# my_tic_tac_toe_board.net
KiCad netlist of a schematic drawn in EAGLE
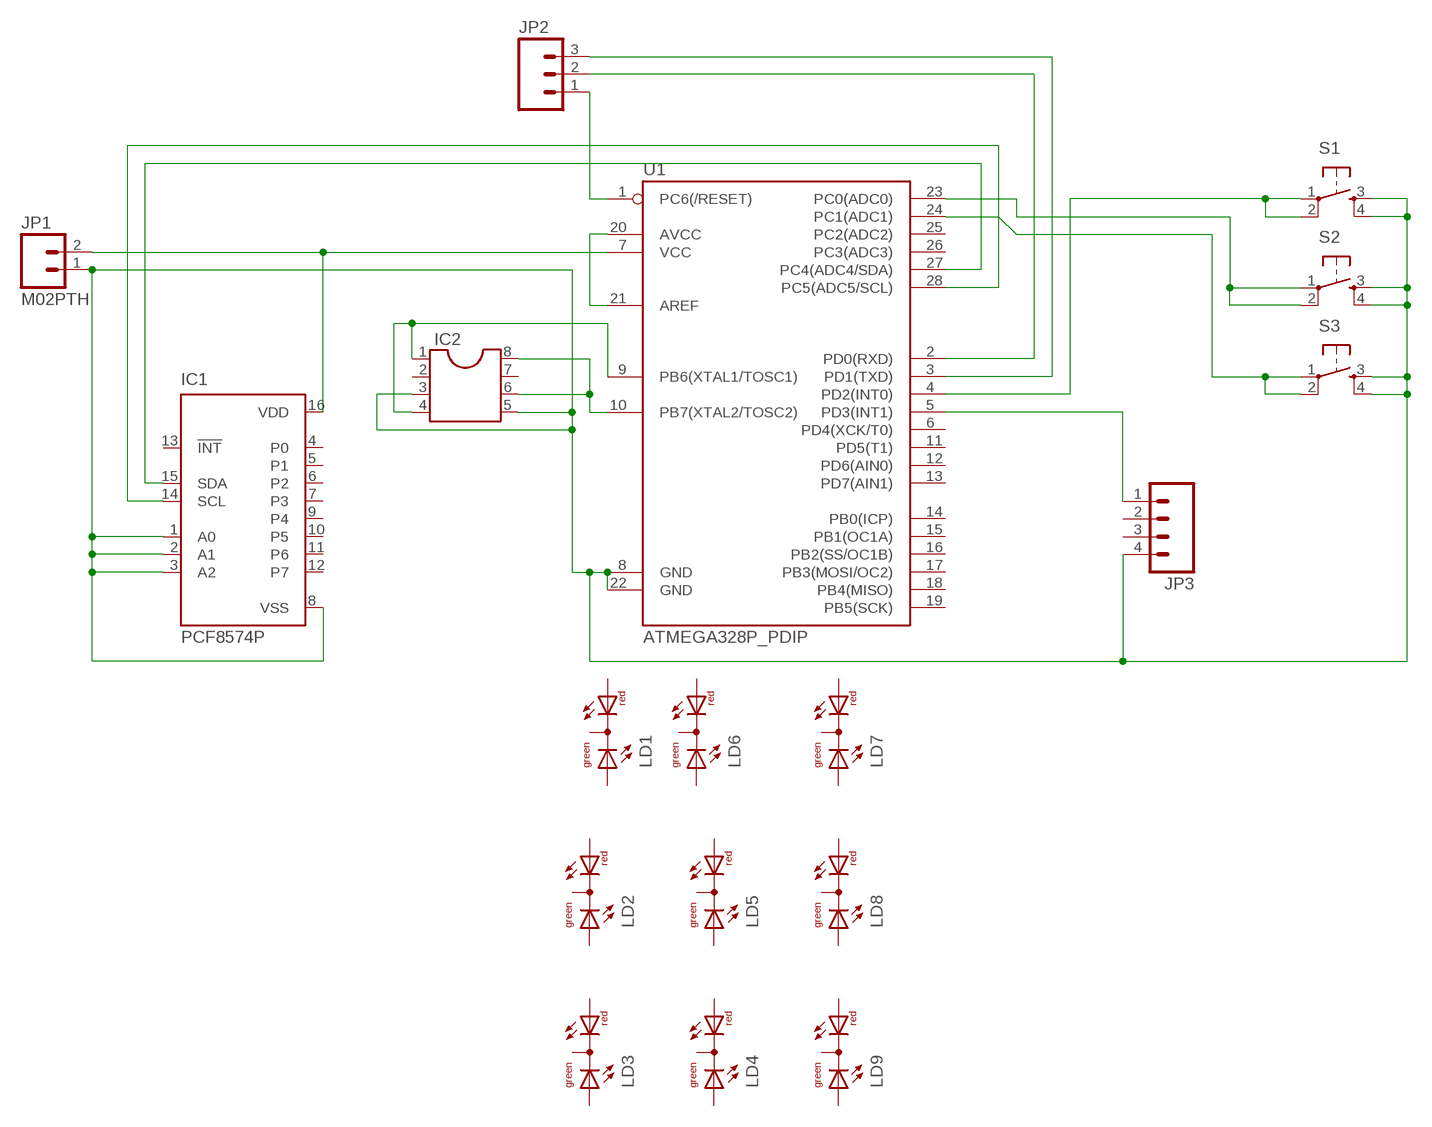
[diagram p0: schematic, sheet 1]

(export (version "E")
  (design (tool "Eeschema 10.0.6"))
  (components
    (comp (ref "IC1")
      (value "PCF8574P")
      (footprint "eagle-import:DIL16")
      (fields (field (name "MPN") "PCF8574PN"))
      (libsource (lib "eagle-import") (part "PCF8574P"))
    )
    (comp (ref "IC2")
      (value "DIL8S")
      (footprint "eagle-import:SOCKET-08")
      (libsource (lib "eagle-import") (part "DIL8S"))
    )
    (comp (ref "JP1")
      (value "M02PTH")
      (footprint "eagle-import:1X02")
      (libsource (lib "eagle-import") (part "M02PTH"))
    )
    (comp (ref "JP2")
      (value "M03PTH")
      (footprint "eagle-import:1X03")
      (libsource (lib "eagle-import") (part "M03PTH"))
    )
    (comp (ref "JP3")
      (value "M04PTH")
      (footprint "eagle-import:1X04")
      (libsource (lib "eagle-import") (part "M04PTH"))
    )
    (comp (ref "LD1")
      (value "DUOLED-RG-C")
      (footprint "eagle-import:DUOLED-C-5MM")
      (libsource (lib "eagle-import") (part "DUOLED-RG-C"))
    )
    (comp (ref "LD2")
      (value "DUOLED-RG-C")
      (footprint "eagle-import:DUOLED-C-5MM")
      (libsource (lib "eagle-import") (part "DUOLED-RG-C"))
    )
    (comp (ref "LD3")
      (value "DUOLED-RG-C")
      (footprint "eagle-import:DUOLED-C-5MM")
      (libsource (lib "eagle-import") (part "DUOLED-RG-C"))
    )
    (comp (ref "LD4")
      (value "DUOLED-RG-C")
      (footprint "eagle-import:DUOLED-C-5MM")
      (libsource (lib "eagle-import") (part "DUOLED-RG-C"))
    )
    (comp (ref "LD5")
      (value "DUOLED-RG-C")
      (footprint "eagle-import:DUOLED-C-5MM")
      (libsource (lib "eagle-import") (part "DUOLED-RG-C"))
    )
    (comp (ref "LD6")
      (value "DUOLED-RG-C")
      (footprint "eagle-import:DUOLED-C-5MM")
      (libsource (lib "eagle-import") (part "DUOLED-RG-C"))
    )
    (comp (ref "LD7")
      (value "DUOLED-RG-C")
      (footprint "eagle-import:DUOLED-C-5MM")
      (libsource (lib "eagle-import") (part "DUOLED-RG-C"))
    )
    (comp (ref "LD8")
      (value "DUOLED-RG-C")
      (footprint "eagle-import:DUOLED-C-5MM")
      (libsource (lib "eagle-import") (part "DUOLED-RG-C"))
    )
    (comp (ref "LD9")
      (value "DUOLED-RG-C")
      (footprint "eagle-import:DUOLED-C-5MM")
      (libsource (lib "eagle-import") (part "DUOLED-RG-C"))
    )
    (comp (ref "S1")
      (value "TAC_SWITCHPTH")
      (footprint "eagle-import:TACTILE-PTH")
      (libsource (lib "eagle-import") (part "TAC_SWITCHPTH"))
    )
    (comp (ref "S2")
      (value "TAC_SWITCHPTH")
      (footprint "eagle-import:TACTILE-PTH")
      (libsource (lib "eagle-import") (part "TAC_SWITCHPTH"))
    )
    (comp (ref "S3")
      (value "TAC_SWITCHPTH")
      (footprint "eagle-import:TACTILE-PTH")
      (libsource (lib "eagle-import") (part "TAC_SWITCHPTH"))
    )
    (comp (ref "U1")
      (value "ATMEGA328P_PDIP")
      (footprint "eagle-import:DIL28-3")
      (libsource (lib "eagle-import") (part "ATMEGA328P_PDIP"))
    )
  )
  (nets
    (net (code "1") (name "Net-(IC1-A0)") (class "Default")
      (node (ref "IC1") (pin "1") (pinfunction "A0_1") (pintype "input"))
      (node (ref "IC1") (pin "2") (pinfunction "A1_2") (pintype "input"))
      (node (ref "IC1") (pin "3") (pinfunction "A2_3") (pintype "input"))
      (node (ref "IC1") (pin "8") (pinfunction "VSS_8") (pintype "power_in"))
      (node (ref "IC2") (pin "3") (pinfunction "3_3") (pintype "passive"))
      (node (ref "IC2") (pin "5") (pinfunction "5_5") (pintype "passive"))
      (node (ref "JP1") (pin "1") (pinfunction "1_1") (pintype "passive"))
      (node (ref "JP3") (pin "4") (pinfunction "4_4") (pintype "passive"))
      (node (ref "S1") (pin "3") (pinfunction "3_3") (pintype "passive"))
      (node (ref "S1") (pin "4") (pinfunction "4_4") (pintype "passive"))
      (node (ref "S2") (pin "3") (pinfunction "3_3") (pintype "passive"))
      (node (ref "S2") (pin "4") (pinfunction "4_4") (pintype "passive"))
      (node (ref "S3") (pin "3") (pinfunction "3_3") (pintype "passive"))
      (node (ref "S3") (pin "4") (pinfunction "4_4") (pintype "passive"))
      (node (ref "U1") (pin "22") (pinfunction "GND_22") (pintype "bidirectional"))
      (node (ref "U1") (pin "8") (pinfunction "GND_8") (pintype "bidirectional"))
    )
    (net (code "2") (name "Net-(IC1-SCL)") (class "Default")
      (node (ref "IC1") (pin "14") (pinfunction "SCL_14") (pintype "input"))
      (node (ref "U1") (pin "28") (pinfunction "PC5(ADC5/SCL)_28") (pintype "bidirectional"))
    )
    (net (code "3") (name "Net-(IC1-SDA)") (class "Default")
      (node (ref "IC1") (pin "15") (pinfunction "SDA_15") (pintype "bidirectional"))
      (node (ref "U1") (pin "27") (pinfunction "PC4(ADC4/SDA)_27") (pintype "bidirectional"))
    )
    (net (code "4") (name "Net-(IC1-VDD)") (class "Default")
      (node (ref "IC1") (pin "16") (pinfunction "VDD_16") (pintype "power_in"))
      (node (ref "JP1") (pin "2") (pinfunction "2_2") (pintype "passive"))
      (node (ref "U1") (pin "20") (pinfunction "AVCC_20") (pintype "bidirectional"))
      (node (ref "U1") (pin "21") (pinfunction "AREF_21") (pintype "bidirectional"))
      (node (ref "U1") (pin "7") (pinfunction "VCC_7") (pintype "bidirectional"))
    )
    (net (code "5") (name "Net-(U1-PB6(XTAL1{slash}TOSC1))") (class "Default")
      (node (ref "IC2") (pin "1") (pinfunction "1_1") (pintype "passive"))
      (node (ref "IC2") (pin "4") (pinfunction "4_4") (pintype "passive"))
      (node (ref "U1") (pin "9") (pinfunction "PB6(XTAL1/TOSC1)_9") (pintype "bidirectional"))
    )
    (net (code "6") (name "Net-(U1-PB7(XTAL2{slash}TOSC2))") (class "Default")
      (node (ref "IC2") (pin "6") (pinfunction "6_6") (pintype "passive"))
      (node (ref "IC2") (pin "8") (pinfunction "8_8") (pintype "passive"))
      (node (ref "U1") (pin "10") (pinfunction "PB7(XTAL2/TOSC2)_10") (pintype "bidirectional"))
    )
    (net (code "7") (name "Net-(U1-PC0(ADC0))") (class "Default")
      (node (ref "S2") (pin "1") (pinfunction "1_1") (pintype "passive"))
      (node (ref "S2") (pin "2") (pinfunction "2_2") (pintype "passive"))
      (node (ref "U1") (pin "23") (pinfunction "PC0(ADC0)_23") (pintype "bidirectional"))
    )
    (net (code "8") (name "Net-(U1-PC1(ADC1))") (class "Default")
      (node (ref "S3") (pin "1") (pinfunction "1_1") (pintype "passive"))
      (node (ref "S3") (pin "2") (pinfunction "2_2") (pintype "passive"))
      (node (ref "U1") (pin "24") (pinfunction "PC1(ADC1)_24") (pintype "bidirectional"))
    )
    (net (code "9") (name "Net-(U1-PC6({slash}RESET))") (class "Default")
      (node (ref "JP2") (pin "1") (pinfunction "1_1") (pintype "passive"))
      (node (ref "U1") (pin "1") (pinfunction "PC6(/RESET)_1") (pintype "bidirectional"))
    )
    (net (code "10") (name "Net-(U1-PD0(RXD))") (class "Default")
      (node (ref "JP2") (pin "2") (pinfunction "2_2") (pintype "passive"))
      (node (ref "U1") (pin "2") (pinfunction "PD0(RXD)_2") (pintype "bidirectional"))
    )
    (net (code "11") (name "Net-(U1-PD1(TXD))") (class "Default")
      (node (ref "JP2") (pin "3") (pinfunction "3_3") (pintype "passive"))
      (node (ref "U1") (pin "3") (pinfunction "PD1(TXD)_3") (pintype "bidirectional"))
    )
    (net (code "12") (name "Net-(U1-PD2(INT0))") (class "Default")
      (node (ref "S1") (pin "1") (pinfunction "1_1") (pintype "passive"))
      (node (ref "S1") (pin "2") (pinfunction "2_2") (pintype "passive"))
      (node (ref "U1") (pin "4") (pinfunction "PD2(INT0)_4") (pintype "bidirectional"))
    )
    (net (code "13") (name "Net-(U1-PD3(INT1))") (class "Default")
      (node (ref "JP3") (pin "1") (pinfunction "1_1") (pintype "passive"))
      (node (ref "U1") (pin "5") (pinfunction "PD3(INT1)_5") (pintype "bidirectional"))
    )
    (net (code "14") (name "unconnected-(IC1-P0-Pad4)") (class "Default")
      (node (ref "IC1") (pin "4") (pinfunction "P0_4") (pintype "bidirectional"))
    )
    (net (code "15") (name "unconnected-(IC1-P1-Pad5)") (class "Default")
      (node (ref "IC1") (pin "5") (pinfunction "P1_5") (pintype "bidirectional"))
    )
    (net (code "16") (name "unconnected-(IC1-P2-Pad6)") (class "Default")
      (node (ref "IC1") (pin "6") (pinfunction "P2_6") (pintype "bidirectional"))
    )
    (net (code "17") (name "unconnected-(IC1-P3-Pad7)") (class "Default")
      (node (ref "IC1") (pin "7") (pinfunction "P3_7") (pintype "bidirectional"))
    )
    (net (code "18") (name "unconnected-(IC1-P4-Pad9)") (class "Default")
      (node (ref "IC1") (pin "9") (pinfunction "P4_9") (pintype "bidirectional"))
    )
    (net (code "19") (name "unconnected-(IC1-P5-Pad10)") (class "Default")
      (node (ref "IC1") (pin "10") (pinfunction "P5_10") (pintype "bidirectional"))
    )
    (net (code "20") (name "unconnected-(IC1-P6-Pad11)") (class "Default")
      (node (ref "IC1") (pin "11") (pinfunction "P6_11") (pintype "bidirectional"))
    )
    (net (code "21") (name "unconnected-(IC1-P7-Pad12)") (class "Default")
      (node (ref "IC1") (pin "12") (pinfunction "P7_12") (pintype "bidirectional"))
    )
    (net (code "22") (name "unconnected-(IC1-~{INT}-Pad13)") (class "Default")
      (node (ref "IC1") (pin "13") (pinfunction "~{INT}_13") (pintype "output"))
    )
    (net (code "23") (name "unconnected-(IC2-Pad2)") (class "Default")
      (node (ref "IC2") (pin "2") (pinfunction "2_2") (pintype "passive"))
    )
    (net (code "24") (name "unconnected-(IC2-Pad7)") (class "Default")
      (node (ref "IC2") (pin "7") (pinfunction "7_7") (pintype "passive"))
    )
    (net (code "25") (name "unconnected-(JP3-Pad2)") (class "Default")
      (node (ref "JP3") (pin "2") (pinfunction "2_2") (pintype "passive"))
    )
    (net (code "26") (name "unconnected-(JP3-Pad3)") (class "Default")
      (node (ref "JP3") (pin "3") (pinfunction "3_3") (pintype "passive"))
    )
    (net (code "27") (name "unconnected-(LD1-AG-PadAX)") (class "Default")
      (node (ref "LD1") (pin "AX") (pinfunction "AG_AX") (pintype "passive"))
    )
    (net (code "28") (name "unconnected-(LD1-PadAR)") (class "Default")
      (node (ref "LD1") (pin "AR") (pinfunction "AR_AR") (pintype "passive"))
    )
    (net (code "29") (name "unconnected-(LD1-PadC)") (class "Default")
      (node (ref "LD1") (pin "C") (pinfunction "C_C") (pintype "passive"))
    )
    (net (code "30") (name "unconnected-(LD2-AG-PadAX)") (class "Default")
      (node (ref "LD2") (pin "AX") (pinfunction "AG_AX") (pintype "passive"))
    )
    (net (code "31") (name "unconnected-(LD2-PadAR)") (class "Default")
      (node (ref "LD2") (pin "AR") (pinfunction "AR_AR") (pintype "passive"))
    )
    (net (code "32") (name "unconnected-(LD2-PadC)") (class "Default")
      (node (ref "LD2") (pin "C") (pinfunction "C_C") (pintype "passive"))
    )
    (net (code "33") (name "unconnected-(LD3-AG-PadAX)") (class "Default")
      (node (ref "LD3") (pin "AX") (pinfunction "AG_AX") (pintype "passive"))
    )
    (net (code "34") (name "unconnected-(LD3-PadAR)") (class "Default")
      (node (ref "LD3") (pin "AR") (pinfunction "AR_AR") (pintype "passive"))
    )
    (net (code "35") (name "unconnected-(LD3-PadC)") (class "Default")
      (node (ref "LD3") (pin "C") (pinfunction "C_C") (pintype "passive"))
    )
    (net (code "36") (name "unconnected-(LD4-AG-PadAX)") (class "Default")
      (node (ref "LD4") (pin "AX") (pinfunction "AG_AX") (pintype "passive"))
    )
    (net (code "37") (name "unconnected-(LD4-PadAR)") (class "Default")
      (node (ref "LD4") (pin "AR") (pinfunction "AR_AR") (pintype "passive"))
    )
    (net (code "38") (name "unconnected-(LD4-PadC)") (class "Default")
      (node (ref "LD4") (pin "C") (pinfunction "C_C") (pintype "passive"))
    )
    (net (code "39") (name "unconnected-(LD5-AG-PadAX)") (class "Default")
      (node (ref "LD5") (pin "AX") (pinfunction "AG_AX") (pintype "passive"))
    )
    (net (code "40") (name "unconnected-(LD5-PadAR)") (class "Default")
      (node (ref "LD5") (pin "AR") (pinfunction "AR_AR") (pintype "passive"))
    )
    (net (code "41") (name "unconnected-(LD5-PadC)") (class "Default")
      (node (ref "LD5") (pin "C") (pinfunction "C_C") (pintype "passive"))
    )
    (net (code "42") (name "unconnected-(LD6-AG-PadAX)") (class "Default")
      (node (ref "LD6") (pin "AX") (pinfunction "AG_AX") (pintype "passive"))
    )
    (net (code "43") (name "unconnected-(LD6-PadAR)") (class "Default")
      (node (ref "LD6") (pin "AR") (pinfunction "AR_AR") (pintype "passive"))
    )
    (net (code "44") (name "unconnected-(LD6-PadC)") (class "Default")
      (node (ref "LD6") (pin "C") (pinfunction "C_C") (pintype "passive"))
    )
    (net (code "45") (name "unconnected-(LD7-AG-PadAX)") (class "Default")
      (node (ref "LD7") (pin "AX") (pinfunction "AG_AX") (pintype "passive"))
    )
    (net (code "46") (name "unconnected-(LD7-PadAR)") (class "Default")
      (node (ref "LD7") (pin "AR") (pinfunction "AR_AR") (pintype "passive"))
    )
    (net (code "47") (name "unconnected-(LD7-PadC)") (class "Default")
      (node (ref "LD7") (pin "C") (pinfunction "C_C") (pintype "passive"))
    )
    (net (code "48") (name "unconnected-(LD8-AG-PadAX)") (class "Default")
      (node (ref "LD8") (pin "AX") (pinfunction "AG_AX") (pintype "passive"))
    )
    (net (code "49") (name "unconnected-(LD8-PadAR)") (class "Default")
      (node (ref "LD8") (pin "AR") (pinfunction "AR_AR") (pintype "passive"))
    )
    (net (code "50") (name "unconnected-(LD8-PadC)") (class "Default")
      (node (ref "LD8") (pin "C") (pinfunction "C_C") (pintype "passive"))
    )
    (net (code "51") (name "unconnected-(LD9-AG-PadAX)") (class "Default")
      (node (ref "LD9") (pin "AX") (pinfunction "AG_AX") (pintype "passive"))
    )
    (net (code "52") (name "unconnected-(LD9-PadAR)") (class "Default")
      (node (ref "LD9") (pin "AR") (pinfunction "AR_AR") (pintype "passive"))
    )
    (net (code "53") (name "unconnected-(LD9-PadC)") (class "Default")
      (node (ref "LD9") (pin "C") (pinfunction "C_C") (pintype "passive"))
    )
    (net (code "54") (name "unconnected-(U1-PB0(ICP)-Pad14)") (class "Default")
      (node (ref "U1") (pin "14") (pinfunction "PB0(ICP)_14") (pintype "bidirectional"))
    )
    (net (code "55") (name "unconnected-(U1-PB1(OC1A)-Pad15)") (class "Default")
      (node (ref "U1") (pin "15") (pinfunction "PB1(OC1A)_15") (pintype "bidirectional"))
    )
    (net (code "56") (name "unconnected-(U1-PB2(SS{slash}OC1B)-Pad16)") (class "Default")
      (node (ref "U1") (pin "16") (pinfunction "PB2(SS/OC1B)_16") (pintype "bidirectional"))
    )
    (net (code "57") (name "unconnected-(U1-PB3(MOSI{slash}OC2)-Pad17)") (class "Default")
      (node (ref "U1") (pin "17") (pinfunction "PB3(MOSI/OC2)_17") (pintype "bidirectional"))
    )
    (net (code "58") (name "unconnected-(U1-PB4(MISO)-Pad18)") (class "Default")
      (node (ref "U1") (pin "18") (pinfunction "PB4(MISO)_18") (pintype "bidirectional"))
    )
    (net (code "59") (name "unconnected-(U1-PB5(SCK)-Pad19)") (class "Default")
      (node (ref "U1") (pin "19") (pinfunction "PB5(SCK)_19") (pintype "bidirectional"))
    )
    (net (code "60") (name "unconnected-(U1-PC2(ADC2)-Pad25)") (class "Default")
      (node (ref "U1") (pin "25") (pinfunction "PC2(ADC2)_25") (pintype "bidirectional"))
    )
    (net (code "61") (name "unconnected-(U1-PC3(ADC3)-Pad26)") (class "Default")
      (node (ref "U1") (pin "26") (pinfunction "PC3(ADC3)_26") (pintype "bidirectional"))
    )
    (net (code "62") (name "unconnected-(U1-PD4(XCK{slash}T0)-Pad6)") (class "Default")
      (node (ref "U1") (pin "6") (pinfunction "PD4(XCK/T0)_6") (pintype "bidirectional"))
    )
    (net (code "63") (name "unconnected-(U1-PD5(T1)-Pad11)") (class "Default")
      (node (ref "U1") (pin "11") (pinfunction "PD5(T1)_11") (pintype "bidirectional"))
    )
    (net (code "64") (name "unconnected-(U1-PD6(AIN0)-Pad12)") (class "Default")
      (node (ref "U1") (pin "12") (pinfunction "PD6(AIN0)_12") (pintype "bidirectional"))
    )
    (net (code "65") (name "unconnected-(U1-PD7(AIN1)-Pad13)") (class "Default")
      (node (ref "U1") (pin "13") (pinfunction "PD7(AIN1)_13") (pintype "bidirectional"))
    )
  )
)
